# Osc.net
KiCad netlist of a schematic drawn in Altium Designer
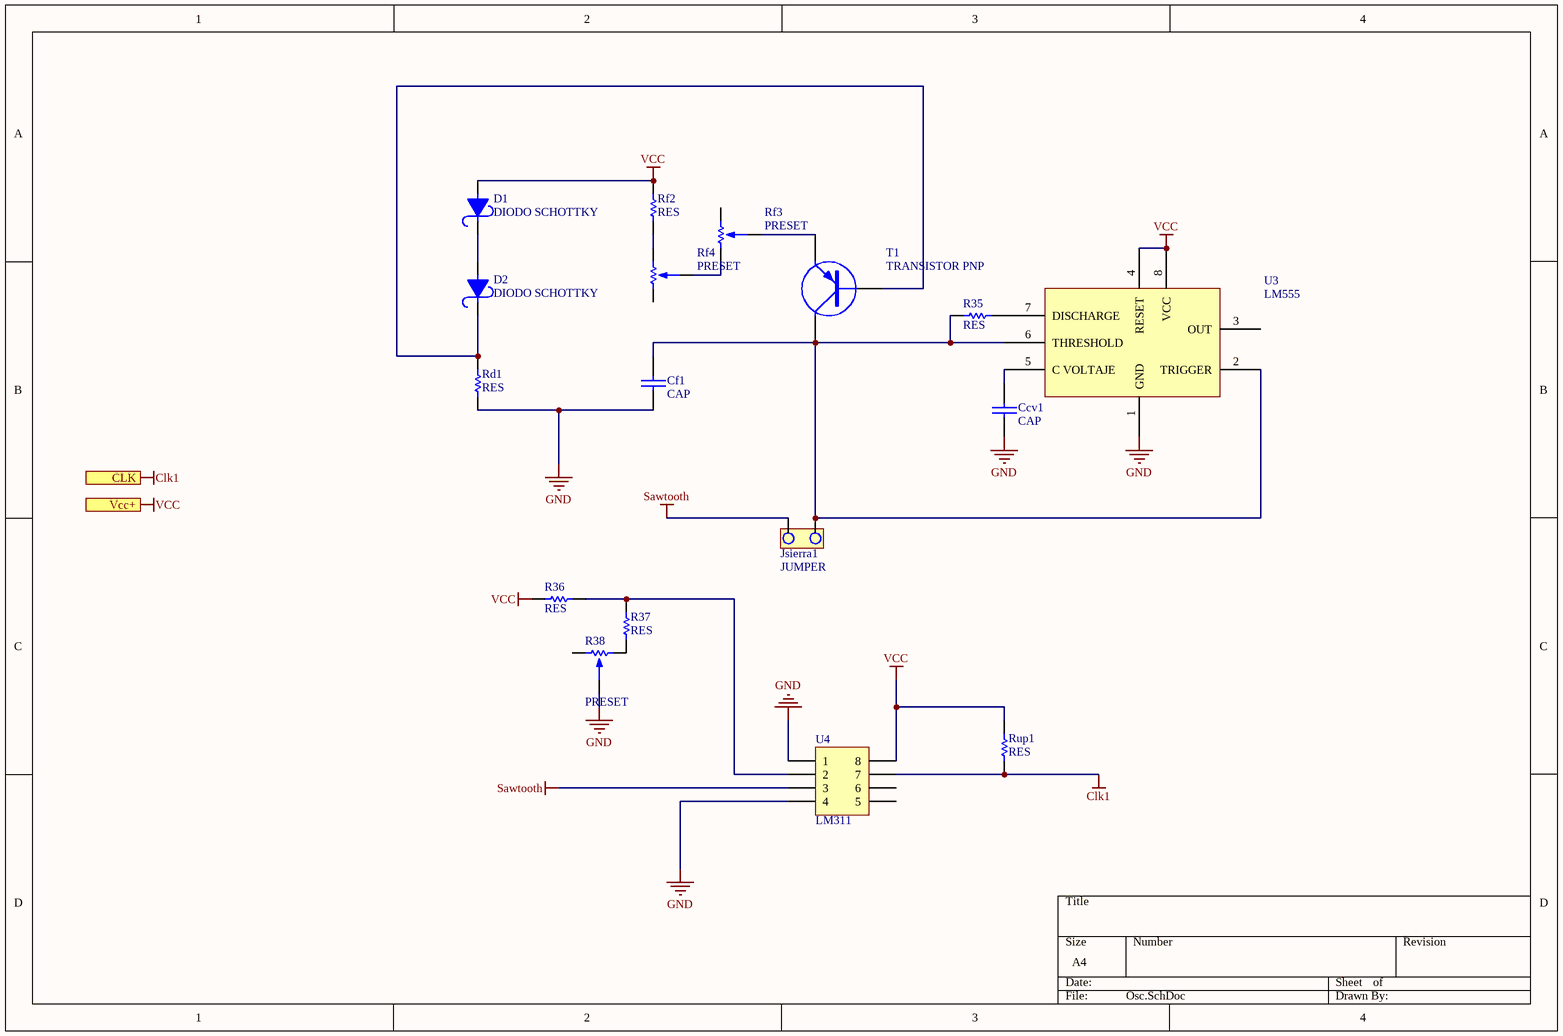
[diagram p0: Osc.SchDoc]

(export (version "E")
  (design (tool "Eeschema 10.0.6"))
  (components
    (comp (ref "Ccv1") (value "CAP") (footprint "0805") (libsource (lib "LIBEBAL") (part "CAP")))
    (comp (ref "Cf1") (value "CAP") (footprint "0805") (libsource (lib "LIBEBAL") (part "CAP")))
    (comp (ref "D1")
      (value "DIODO SCHOTTKY")
      (footprint "DO41")
      (libsource (lib "LIBEBAL") (part "DIODO SCHOTTKY"))
    )
    (comp (ref "D2")
      (value "DIODO SCHOTTKY")
      (footprint "DO41")
      (libsource (lib "LIBEBAL") (part "DIODO SCHOTTKY"))
    )
    (comp (ref "Jsierra1") (value "JUMPER") (footprint "JUMPER2") (libsource (lib "LIBEBAL") (part "JUMPER")))
    (comp (ref "R35") (value "RES") (footprint "0805") (libsource (lib "LIBEBAL") (part "RES")))
    (comp (ref "R36") (value "RES") (footprint "0805") (libsource (lib "LIBEBAL") (part "RES")))
    (comp (ref "R37") (value "RES") (footprint "0805") (libsource (lib "LIBEBAL") (part "RES")))
    (comp (ref "R38") (value "PRESET") (footprint "PRESET V") (libsource (lib "LIBEBAL") (part "PRESET")))
    (comp (ref "Rd1") (value "RES") (footprint "0805") (libsource (lib "LIBEBAL") (part "RES")))
    (comp (ref "Rf2") (value "RES") (footprint "0805") (libsource (lib "LIBEBAL") (part "RES")))
    (comp (ref "Rf3") (value "PRESET") (footprint "PRESET V") (libsource (lib "LIBEBAL") (part "PRESET")))
    (comp (ref "Rf4") (value "PRESET") (footprint "PRESET V") (libsource (lib "LIBEBAL") (part "PRESET")))
    (comp (ref "Rup1") (value "RES") (footprint "0805") (libsource (lib "LIBEBAL") (part "RES")))
    (comp (ref "T1")
      (value "TRANSISTOR PNP")
      (footprint "TO92")
      (libsource (lib "LIBEBAL") (part "TRANSISTOR PNP"))
    )
    (comp (ref "U3")
      (value "LM555")
      (footprint "DIP8")
      (description "Timer")
      (libsource (lib "LIBEBAL") (part "LM555"))
    )
    (comp (ref "U4") (value "LM311") (footprint "DIP8") (libsource (lib "LIBEBAL") (part "IC_DIP8")))
  )
  (nets
    (net (code "1") (name "Clk1") (class "Default")
      (node (ref "Rup1") (pin "1") (pinfunction "1_1") (pintype "passive"))
      (node (ref "U4") (pin "7") (pinfunction "7_7") (pintype "passive"))
    )
    (net (code "2") (name "GND") (class "Default")
      (node (ref "Ccv1") (pin "2") (pinfunction "2_2") (pintype "passive"))
      (node (ref "Cf1") (pin "2") (pinfunction "2_2") (pintype "passive"))
      (node (ref "R38") (pin "2") (pinfunction "2_2") (pintype "passive"))
      (node (ref "Rd1") (pin "1") (pinfunction "1_1") (pintype "passive"))
      (node (ref "U3") (pin "1") (pinfunction "GND_1") (pintype "passive"))
      (node (ref "U4") (pin "1") (pinfunction "1_1") (pintype "passive"))
      (node (ref "U4") (pin "4") (pinfunction "4_4") (pintype "passive"))
    )
    (net (code "3") (name "Net-(D1-Pad2)") (class "Default")
      (node (ref "D1") (pin "2") (pinfunction "2_2") (pintype "passive"))
      (node (ref "D2") (pin "1") (pinfunction "1_1") (pintype "passive"))
    )
    (net (code "4") (name "Net-(R36-Pad1)") (class "Default")
      (node (ref "R36") (pin "1") (pinfunction "1_1") (pintype "passive"))
      (node (ref "R37") (pin "1") (pinfunction "1_1") (pintype "passive"))
      (node (ref "U4") (pin "2") (pinfunction "2_2") (pintype "passive"))
    )
    (net (code "5") (name "Net-(R37-Pad2)") (class "Default")
      (node (ref "R37") (pin "2") (pinfunction "2_2") (pintype "passive"))
      (node (ref "R38") (pin "1") (pinfunction "1_1") (pintype "passive"))
    )
    (net (code "6") (name "Net-(Rf2-Pad1)") (class "Default")
      (node (ref "Rf2") (pin "1") (pinfunction "1_1") (pintype "passive"))
      (node (ref "Rf4") (pin "1") (pinfunction "1_1") (pintype "passive"))
    )
    (net (code "7") (name "Net-(Rf3-Pad3)") (class "Default")
      (node (ref "Rf3") (pin "3") (pinfunction "3_3") (pintype "passive"))
      (node (ref "Rf4") (pin "2") (pinfunction "2_2") (pintype "passive"))
    )
    (net (code "8") (name "Net-(T1-B)") (class "Default")
      (node (ref "D2") (pin "2") (pinfunction "2_2") (pintype "passive"))
      (node (ref "Rd1") (pin "2") (pinfunction "2_2") (pintype "passive"))
      (node (ref "T1") (pin "1") (pinfunction "B_1") (pintype "passive"))
    )
    (net (code "9") (name "Net-(T1-C)") (class "Default")
      (node (ref "Cf1") (pin "1") (pinfunction "1_1") (pintype "passive"))
      (node (ref "Jsierra1") (pin "2") (pinfunction "2_2") (pintype "passive"))
      (node (ref "R35") (pin "1") (pinfunction "1_1") (pintype "passive"))
      (node (ref "T1") (pin "2") (pinfunction "C_2") (pintype "passive"))
      (node (ref "U3") (pin "2") (pinfunction "TRIGGER_2") (pintype "passive"))
      (node (ref "U3") (pin "6") (pinfunction "THRESHOLD_6") (pintype "passive"))
    )
    (net (code "10") (name "Net-(T1-E)") (class "Default")
      (node (ref "Rf3") (pin "2") (pinfunction "2_2") (pintype "passive"))
      (node (ref "T1") (pin "3") (pinfunction "E_3") (pintype "passive"))
    )
    (net (code "11") (name "Net-(U3-C_VOLTAJE)") (class "Default")
      (node (ref "Ccv1") (pin "1") (pinfunction "1_1") (pintype "passive"))
      (node (ref "U3") (pin "5") (pinfunction "C_VOLTAJE_5") (pintype "passive"))
    )
    (net (code "12") (name "Net-(U3-DISCHARGE)") (class "Default")
      (node (ref "R35") (pin "2") (pinfunction "2_2") (pintype "passive"))
      (node (ref "U3") (pin "7") (pinfunction "DISCHARGE_7") (pintype "passive"))
    )
    (net (code "13") (name "Sawtooth") (class "Default")
      (node (ref "Jsierra1") (pin "1") (pinfunction "1_1") (pintype "passive"))
      (node (ref "U4") (pin "3") (pinfunction "3_3") (pintype "passive"))
    )
    (net (code "14") (name "VCC") (class "Default")
      (node (ref "D1") (pin "1") (pinfunction "1_1") (pintype "passive"))
      (node (ref "R36") (pin "2") (pinfunction "2_2") (pintype "passive"))
      (node (ref "Rf2") (pin "2") (pinfunction "2_2") (pintype "passive"))
      (node (ref "Rup1") (pin "2") (pinfunction "2_2") (pintype "passive"))
      (node (ref "U3") (pin "4") (pinfunction "RESET_4") (pintype "passive"))
      (node (ref "U3") (pin "8") (pinfunction "VCC_8") (pintype "passive"))
      (node (ref "U4") (pin "8") (pinfunction "8_8") (pintype "passive"))
    )
    (net (code "15") (name "unconnected-(R38-Pad3)") (class "Default")
      (node (ref "R38") (pin "3") (pinfunction "3_3") (pintype "passive"))
    )
    (net (code "16") (name "unconnected-(Rf3-Pad1)") (class "Default")
      (node (ref "Rf3") (pin "1") (pinfunction "1_1") (pintype "passive"))
    )
    (net (code "17") (name "unconnected-(Rf4-Pad3)") (class "Default")
      (node (ref "Rf4") (pin "3") (pinfunction "3_3") (pintype "passive"))
    )
    (net (code "18") (name "unconnected-(U3-OUT-Pad3)") (class "Default")
      (node (ref "U3") (pin "3") (pinfunction "OUT_3") (pintype "passive"))
    )
    (net (code "19") (name "unconnected-(U4-Pad5)") (class "Default")
      (node (ref "U4") (pin "5") (pinfunction "5_5") (pintype "passive"))
    )
    (net (code "20") (name "unconnected-(U4-Pad6)") (class "Default")
      (node (ref "U4") (pin "6") (pinfunction "6_6") (pintype "passive"))
    )
  )
)
